# EmbeddedPeripherals.net
KiCad netlist of a schematic drawn in Altium Designer
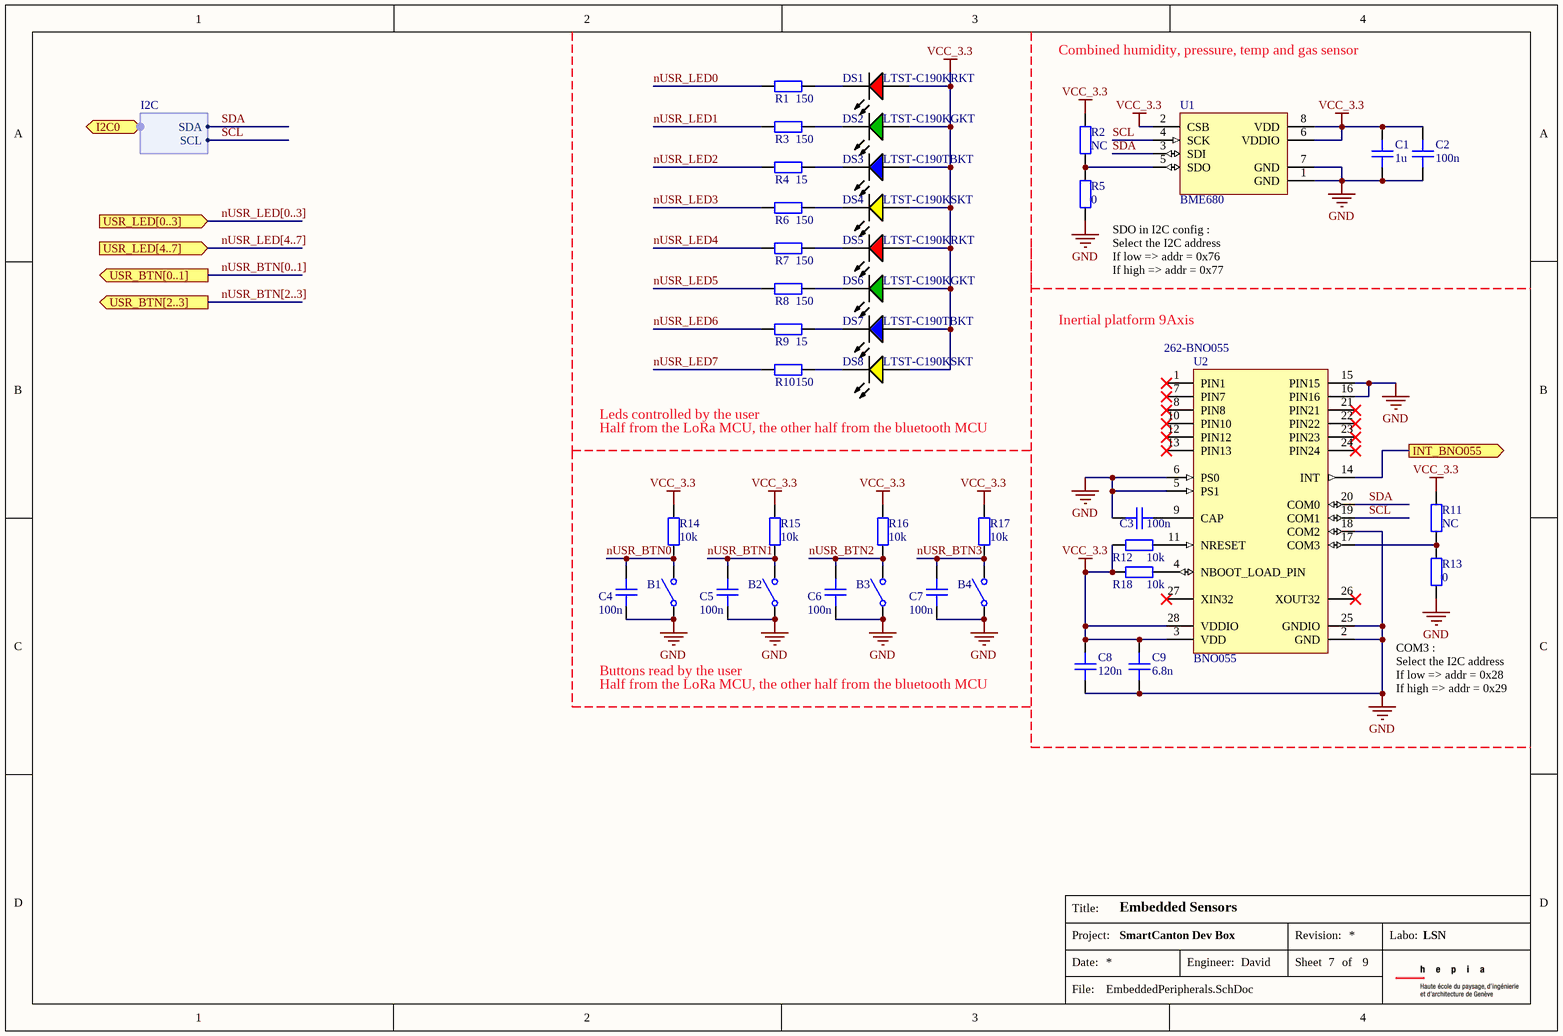
[diagram p0: EmbeddedPeripherals.SchDoc]

(export (version "E")
  (design (tool "Eeschema 10.0.6"))
  (components
    (comp (ref "B1")
      (value "653-B3U-1000P")
      (footprint "B3U-1000P")
      (libsource (lib "eSurf_handle") (part "PUSH_BUTTON"))
    )
    (comp (ref "B2")
      (value "653-B3U-1000P")
      (footprint "B3U-1000P")
      (libsource (lib "eSurf_handle") (part "PUSH_BUTTON"))
    )
    (comp (ref "B3")
      (value "653-B3U-1000P")
      (footprint "B3U-1000P")
      (libsource (lib "eSurf_handle") (part "PUSH_BUTTON"))
    )
    (comp (ref "B4")
      (value "653-B3U-1000P")
      (footprint "B3U-1000P")
      (libsource (lib "eSurf_handle") (part "PUSH_BUTTON"))
    )
    (comp (ref "C1")
      (value "1u")
      (footprint "CAPC1608X08")
      (description "MLCC Capacitor 1608")
      (libsource (lib "HEPIA Vault") (part "CMP-001-0010-A.3"))
    )
    (comp (ref "C2")
      (value "100n")
      (footprint "CAPC1608X08")
      (description "MLCC Capacitor 1608")
      (libsource (lib "HEPIA Vault") (part "Capacitor"))
    )
    (comp (ref "C3")
      (value "100n")
      (footprint "CAPC1608X08")
      (description "MLCC Capacitor 1608")
      (libsource (lib "HEPIA Vault") (part "CMP-001-0010-A.3"))
    )
    (comp (ref "C4")
      (value "100n")
      (footprint "CAPC1608X08")
      (description "MLCC Capacitor 1608")
      (libsource (lib "HEPIA Vault") (part "CMP-001-0010-A.3"))
    )
    (comp (ref "C5")
      (value "100n")
      (footprint "CAPC1608X08")
      (description "MLCC Capacitor 1608")
      (libsource (lib "HEPIA Vault") (part "CMP-001-0010-A.3"))
    )
    (comp (ref "C6")
      (value "100n")
      (footprint "CAPC1608X08")
      (description "MLCC Capacitor 1608")
      (libsource (lib "HEPIA Vault") (part "CMP-001-0010-A.3"))
    )
    (comp (ref "C7")
      (value "100n")
      (footprint "CAPC1608X08")
      (description "MLCC Capacitor 1608")
      (libsource (lib "HEPIA Vault") (part "CMP-001-0010-A.3"))
    )
    (comp (ref "C8")
      (value "120n")
      (footprint "CAPC1608X08")
      (description "MLCC Capacitor 1608")
      (libsource (lib "HEPIA Vault") (part "CMP-001-0010-A.3"))
    )
    (comp (ref "C9")
      (value "6.8n")
      (footprint "CAPC1608X08")
      (description "MLCC Capacitor 1608")
      (libsource (lib "HEPIA Vault") (part "CMP-001-0010-A.3"))
    )
    (comp (ref "DS1")
      (value "LTST-C190KRKT")
      (footprint "LTST-C191KRKT_V")
      (description "LED Uni-Color Red, 62.5 mW, 5 V, -30 to 85 degC, 2-Pin SMD, RoHS, Tape and Reel")
      (fields (field (name "TOLERANCE") "20%"))
      (libsource (lib "HEPIA Vault") (part "LED-RED-AK-2"))
    )
    (comp (ref "DS2")
      (value "LTST-C190KGKT")
      (footprint "LITE-ON-LTST-C190GKT-2_V")
      (description "LED Uni-Color Green, 75 mW, 5 V, -30 to 85 degC, 2-Pin SMD, RoHS, Tape and Reel")
      (fields (field (name "MANUFACTURER") "Lite-On"))
      (libsource (lib "HEPIA Vault") (part "LED_GREEN_A1K2-2"))
    )
    (comp (ref "DS3")
      (value "LTST-C190TBKT")
      (footprint "LTST-C190TBKT-2_V")
      (description "Single Color Chip LED, 2.8 to 3.8 V, 28 to 180 mcd, -20 to 80 degC, 2-Pin SMD, RoHS, Tape and Reel")
      (libsource (lib "HEPIA Vault") (part "LED-BLUE-AK-2"))
    )
    (comp (ref "DS4")
      (value "LTST-C190KSKT")
      (footprint "LTST-C190KSKT_V")
      (description "LED Uni-Color Yellow, 75 mW, 30 mA, -30 to 85 degC, 2-Pin SMD, RoHS, Tape and Reel")
      (fields (field (name "TOLERANCE") "1%"))
      (libsource (lib "HEPIA Vault") (part "LED-YELLOW-AK-2"))
    )
    (comp (ref "DS5")
      (value "LTST-C190KRKT")
      (footprint "LTST-C191KRKT_V")
      (description "LED Uni-Color Red, 62.5 mW, 5 V, -30 to 85 degC, 2-Pin SMD, RoHS, Tape and Reel")
      (fields (field (name "TOLERANCE") "20%"))
      (libsource (lib "HEPIA Vault") (part "LED-RED-AK-2"))
    )
    (comp (ref "DS6")
      (value "LTST-C190KGKT")
      (footprint "LITE-ON-LTST-C190GKT-2_V")
      (description "LED Uni-Color Green, 75 mW, 5 V, -30 to 85 degC, 2-Pin SMD, RoHS, Tape and Reel")
      (fields (field (name "MANUFACTURER") "Lite-On"))
      (libsource (lib "HEPIA Vault") (part "LED_GREEN_A1K2-2"))
    )
    (comp (ref "DS7")
      (value "LTST-C190TBKT")
      (footprint "LTST-C190TBKT-2_V")
      (description "Single Color Chip LED, 2.8 to 3.8 V, 28 to 180 mcd, -20 to 80 degC, 2-Pin SMD, RoHS, Tape and Reel")
      (libsource (lib "HEPIA Vault") (part "LED-BLUE-AK-2"))
    )
    (comp (ref "DS8")
      (value "LTST-C190KSKT")
      (footprint "LTST-C190KSKT_V")
      (description "LED Uni-Color Yellow, 75 mW, 30 mA, -30 to 85 degC, 2-Pin SMD, RoHS, Tape and Reel")
      (fields (field (name "TOLERANCE") "1%"))
      (libsource (lib "HEPIA Vault") (part "LED-YELLOW-AK-2"))
    )
    (comp (ref "R1")
      (value "150")
      (footprint "RESC1608X06")
      (description "1608 resistor")
      (libsource (lib "HEPIA Vault") (part "CMP-001-0005-A.4"))
    )
    (comp (ref "R2")
      (value "NC")
      (footprint "RESC1608X06")
      (description "1608 resistor")
      (libsource (lib "") (part "CMP-001-0005-A.4_1"))
    )
    (comp (ref "R3")
      (value "150")
      (footprint "RESC1608X06")
      (description "1608 resistor")
      (libsource (lib "HEPIA Vault") (part "CMP-001-0005-A.4"))
    )
    (comp (ref "R4")
      (value "15")
      (footprint "RESC1608X06")
      (description "1608 resistor")
      (libsource (lib "HEPIA Vault") (part "CMP-001-0005-A.4"))
    )
    (comp (ref "R5")
      (value "0")
      (footprint "RESC1608X06")
      (description "1608 resistor")
      (libsource (lib "") (part "CMP-001-0005-A.4_1"))
    )
    (comp (ref "R6")
      (value "150")
      (footprint "RESC1608X06")
      (description "1608 resistor")
      (libsource (lib "HEPIA Vault") (part "CMP-001-0005-A.4"))
    )
    (comp (ref "R7")
      (value "150")
      (footprint "RESC1608X06")
      (description "1608 resistor")
      (libsource (lib "HEPIA Vault") (part "CMP-001-0005-A.4"))
    )
    (comp (ref "R8")
      (value "150")
      (footprint "RESC1608X06")
      (description "1608 resistor")
      (libsource (lib "HEPIA Vault") (part "CMP-001-0005-A.4"))
    )
    (comp (ref "R9")
      (value "15")
      (footprint "RESC1608X06")
      (description "1608 resistor")
      (libsource (lib "HEPIA Vault") (part "CMP-001-0005-A.4"))
    )
    (comp (ref "R10")
      (value "150")
      (footprint "RESC1608X06")
      (description "1608 resistor")
      (libsource (lib "HEPIA Vault") (part "CMP-001-0005-A.4"))
    )
    (comp (ref "R11")
      (value "NC")
      (footprint "RESC1608X06")
      (description "1608 resistor")
      (libsource (lib "") (part "CMP-001-0005-A.4_1"))
    )
    (comp (ref "R12")
      (value "10k")
      (footprint "RESC1608X06")
      (description "1608 resistor")
      (libsource (lib "HEPIA Vault") (part "CMP-001-0005-A.4"))
    )
    (comp (ref "R13")
      (value "0")
      (footprint "RESC1608X06")
      (description "1608 resistor")
      (libsource (lib "") (part "CMP-001-0005-A.4_1"))
    )
    (comp (ref "R14")
      (value "10k")
      (footprint "RESC1608X06")
      (description "1608 resistor")
      (libsource (lib "") (part "CMP-001-0005-A.4_1"))
    )
    (comp (ref "R15")
      (value "10k")
      (footprint "RESC1608X06")
      (description "1608 resistor")
      (libsource (lib "") (part "CMP-001-0005-A.4_1"))
    )
    (comp (ref "R16")
      (value "10k")
      (footprint "RESC1608X06")
      (description "1608 resistor")
      (libsource (lib "") (part "CMP-001-0005-A.4_1"))
    )
    (comp (ref "R17")
      (value "10k")
      (footprint "RESC1608X06")
      (description "1608 resistor")
      (libsource (lib "") (part "CMP-001-0005-A.4_1"))
    )
    (comp (ref "R18")
      (value "10k")
      (footprint "RESC1608X06")
      (description "1608 resistor")
      (libsource (lib "HEPIA Vault") (part "CMP-001-0005-A.4"))
    )
    (comp (ref "U1")
      (value "BME680")
      (footprint "LGA-8-30x30x09")
      (description "Combined himidity, pressure, temp and gas sensor")
      (libsource (lib "HEPIA Vault") (part "BME680"))
    )
    (comp (ref "U2")
      (value "BNO055")
      (footprint "BOSC-LGA-28_N")
      (fields
        (field (name "MANUFACTURER") "Bosch Sensortec")
        (field (name "SUPPLIER PART NUMBER 1") "262-BNO055")
      )
      (libsource (lib "HEPIA Vault") (part "CMP-00007-A.1"))
    )
  )
  (nets
    (net (code "2") (name "/INT_BNO055") (class "Default")
      (node (ref "U2") (pin "14") (pinfunction "INT_14") (pintype "output"))
    )
    (net (code "3") (name "/SCL") (class "Default")
      (node (ref "U1") (pin "4") (pinfunction "SCK_4") (pintype "input"))
      (node (ref "U2") (pin "19") (pinfunction "COM1_19") (pintype "bidirectional"))
    )
    (net (code "4") (name "/SDA") (class "Default")
      (node (ref "U1") (pin "3") (pinfunction "SDI_3") (pintype "bidirectional"))
      (node (ref "U2") (pin "20") (pinfunction "COM0_20") (pintype "bidirectional"))
    )
    (net (code "5") (name "/nUSR_BTN0") (class "Default")
      (node (ref "B1") (pin "2") (pinfunction "2_2") (pintype "passive"))
      (node (ref "C4") (pin "1") (pinfunction "1_1") (pintype "passive"))
      (node (ref "R14") (pin "1") (pinfunction "1_1") (pintype "passive"))
    )
    (net (code "6") (name "/nUSR_BTN1") (class "Default")
      (node (ref "B2") (pin "2") (pinfunction "2_2") (pintype "passive"))
      (node (ref "C5") (pin "1") (pinfunction "1_1") (pintype "passive"))
      (node (ref "R15") (pin "1") (pinfunction "1_1") (pintype "passive"))
    )
    (net (code "7") (name "/nUSR_BTN2") (class "Default")
      (node (ref "B3") (pin "2") (pinfunction "2_2") (pintype "passive"))
      (node (ref "C6") (pin "1") (pinfunction "1_1") (pintype "passive"))
      (node (ref "R16") (pin "1") (pinfunction "1_1") (pintype "passive"))
    )
    (net (code "8") (name "/nUSR_BTN3") (class "Default")
      (node (ref "B4") (pin "2") (pinfunction "2_2") (pintype "passive"))
      (node (ref "C7") (pin "1") (pinfunction "1_1") (pintype "passive"))
      (node (ref "R17") (pin "1") (pinfunction "1_1") (pintype "passive"))
    )
    (net (code "11") (name "/nUSR_LED0") (class "Default")
      (node (ref "R1") (pin "1") (pinfunction "1_1") (pintype "passive"))
    )
    (net (code "12") (name "/nUSR_LED1") (class "Default")
      (node (ref "R3") (pin "1") (pinfunction "1_1") (pintype "passive"))
    )
    (net (code "13") (name "/nUSR_LED2") (class "Default")
      (node (ref "R4") (pin "1") (pinfunction "1_1") (pintype "passive"))
    )
    (net (code "14") (name "/nUSR_LED3") (class "Default")
      (node (ref "R6") (pin "1") (pinfunction "1_1") (pintype "passive"))
    )
    (net (code "15") (name "/nUSR_LED4") (class "Default")
      (node (ref "R7") (pin "1") (pinfunction "1_1") (pintype "passive"))
    )
    (net (code "16") (name "/nUSR_LED5") (class "Default")
      (node (ref "R8") (pin "1") (pinfunction "1_1") (pintype "passive"))
    )
    (net (code "17") (name "/nUSR_LED6") (class "Default")
      (node (ref "R9") (pin "1") (pinfunction "1_1") (pintype "passive"))
    )
    (net (code "18") (name "/nUSR_LED7") (class "Default")
      (node (ref "R10") (pin "1") (pinfunction "1_1") (pintype "passive"))
    )
    (net (code "22") (name "GND") (class "Default")
      (node (ref "B1") (pin "1") (pinfunction "1_1") (pintype "passive"))
      (node (ref "B2") (pin "1") (pinfunction "1_1") (pintype "passive"))
      (node (ref "B3") (pin "1") (pinfunction "1_1") (pintype "passive"))
      (node (ref "B4") (pin "1") (pinfunction "1_1") (pintype "passive"))
      (node (ref "C1") (pin "1") (pinfunction "1_1") (pintype "passive"))
      (node (ref "C2") (pin "1") (pinfunction "1_1") (pintype "passive"))
      (node (ref "C3") (pin "2") (pinfunction "2_2") (pintype "passive"))
      (node (ref "C4") (pin "2") (pinfunction "2_2") (pintype "passive"))
      (node (ref "C5") (pin "2") (pinfunction "2_2") (pintype "passive"))
      (node (ref "C6") (pin "2") (pinfunction "2_2") (pintype "passive"))
      (node (ref "C7") (pin "2") (pinfunction "2_2") (pintype "passive"))
      (node (ref "C8") (pin "1") (pinfunction "1_1") (pintype "passive"))
      (node (ref "C9") (pin "1") (pinfunction "1_1") (pintype "passive"))
      (node (ref "R13") (pin "1") (pinfunction "1_1") (pintype "passive"))
      (node (ref "R5") (pin "1") (pinfunction "1_1") (pintype "passive"))
      (node (ref "U1") (pin "1") (pinfunction "GND_1") (pintype "power_in"))
      (node (ref "U1") (pin "7") (pinfunction "GND_7") (pintype "power_in"))
      (node (ref "U2") (pin "15") (pinfunction "PIN15_15") (pintype "power_in"))
      (node (ref "U2") (pin "16") (pinfunction "PIN16_16") (pintype "power_in"))
      (node (ref "U2") (pin "18") (pinfunction "COM2_18") (pintype "bidirectional"))
      (node (ref "U2") (pin "2") (pinfunction "GND_2") (pintype "power_in"))
      (node (ref "U2") (pin "25") (pinfunction "GNDIO_25") (pintype "power_in"))
      (node (ref "U2") (pin "5") (pinfunction "PS1_5") (pintype "input"))
      (node (ref "U2") (pin "6") (pinfunction "PS0_6") (pintype "input"))
    )
    (net (code "23") (name "Net-(DS1-K)") (class "Default")
      (node (ref "DS1") (pin "2") (pinfunction "K_2") (pintype "passive"))
      (node (ref "R1") (pin "2") (pinfunction "2_2") (pintype "passive"))
    )
    (net (code "24") (name "Net-(DS2-K)") (class "Default")
      (node (ref "DS2") (pin "2") (pinfunction "K_2") (pintype "passive"))
      (node (ref "R3") (pin "2") (pinfunction "2_2") (pintype "passive"))
    )
    (net (code "25") (name "Net-(DS3-K)") (class "Default")
      (node (ref "DS3") (pin "2") (pinfunction "K_2") (pintype "passive"))
      (node (ref "R4") (pin "2") (pinfunction "2_2") (pintype "passive"))
    )
    (net (code "26") (name "Net-(DS4-K)") (class "Default")
      (node (ref "DS4") (pin "2") (pinfunction "K_2") (pintype "passive"))
      (node (ref "R6") (pin "2") (pinfunction "2_2") (pintype "passive"))
    )
    (net (code "27") (name "Net-(DS5-K)") (class "Default")
      (node (ref "DS5") (pin "2") (pinfunction "K_2") (pintype "passive"))
      (node (ref "R7") (pin "2") (pinfunction "2_2") (pintype "passive"))
    )
    (net (code "28") (name "Net-(DS6-K)") (class "Default")
      (node (ref "DS6") (pin "2") (pinfunction "K_2") (pintype "passive"))
      (node (ref "R8") (pin "2") (pinfunction "2_2") (pintype "passive"))
    )
    (net (code "29") (name "Net-(DS7-K)") (class "Default")
      (node (ref "DS7") (pin "2") (pinfunction "K_2") (pintype "passive"))
      (node (ref "R9") (pin "2") (pinfunction "2_2") (pintype "passive"))
    )
    (net (code "30") (name "Net-(DS8-K)") (class "Default")
      (node (ref "DS8") (pin "2") (pinfunction "K_2") (pintype "passive"))
      (node (ref "R10") (pin "2") (pinfunction "2_2") (pintype "passive"))
    )
    (net (code "31") (name "Net-(U1-SDO)") (class "Default")
      (node (ref "R2") (pin "1") (pinfunction "1_1") (pintype "passive"))
      (node (ref "R5") (pin "2") (pinfunction "2_2") (pintype "passive"))
      (node (ref "U1") (pin "5") (pinfunction "SDO_5") (pintype "bidirectional"))
    )
    (net (code "32") (name "Net-(U2-CAP)") (class "Default")
      (node (ref "C3") (pin "1") (pinfunction "1_1") (pintype "passive"))
      (node (ref "U2") (pin "9") (pinfunction "CAP_9") (pintype "passive"))
    )
    (net (code "33") (name "Net-(U2-COM3)") (class "Default")
      (node (ref "R11") (pin "1") (pinfunction "1_1") (pintype "passive"))
      (node (ref "R13") (pin "2") (pinfunction "2_2") (pintype "passive"))
      (node (ref "U2") (pin "17") (pinfunction "COM3_17") (pintype "bidirectional"))
    )
    (net (code "34") (name "Net-(U2-NBOOT_LOAD_PIN)") (class "Default")
      (node (ref "R18") (pin "2") (pinfunction "2_2") (pintype "passive"))
      (node (ref "U2") (pin "4") (pinfunction "NBOOT_LOAD_PIN_4") (pintype "bidirectional"))
    )
    (net (code "35") (name "Net-(U2-NRESET)") (class "Default")
      (node (ref "R12") (pin "2") (pinfunction "2_2") (pintype "passive"))
      (node (ref "U2") (pin "11") (pinfunction "NRESET_11") (pintype "input"))
    )
    (net (code "36") (name "VCC_3.3") (class "Default")
      (node (ref "C1") (pin "2") (pinfunction "2_2") (pintype "passive"))
      (node (ref "C2") (pin "2") (pinfunction "2_2") (pintype "passive"))
      (node (ref "C8") (pin "2") (pinfunction "2_2") (pintype "passive"))
      (node (ref "C9") (pin "2") (pinfunction "2_2") (pintype "passive"))
      (node (ref "DS1") (pin "1") (pinfunction "A_1") (pintype "passive"))
      (node (ref "DS2") (pin "1") (pinfunction "A_1") (pintype "passive"))
      (node (ref "DS3") (pin "1") (pinfunction "A_1") (pintype "passive"))
      (node (ref "DS4") (pin "1") (pinfunction "A_1") (pintype "passive"))
      (node (ref "DS5") (pin "1") (pinfunction "A_1") (pintype "passive"))
      (node (ref "DS6") (pin "1") (pinfunction "A_1") (pintype "passive"))
      (node (ref "DS7") (pin "1") (pinfunction "A_1") (pintype "passive"))
      (node (ref "DS8") (pin "1") (pinfunction "A_1") (pintype "passive"))
      (node (ref "R11") (pin "2") (pinfunction "2_2") (pintype "passive"))
      (node (ref "R12") (pin "1") (pinfunction "1_1") (pintype "passive"))
      (node (ref "R14") (pin "2") (pinfunction "2_2") (pintype "passive"))
      (node (ref "R15") (pin "2") (pinfunction "2_2") (pintype "passive"))
      (node (ref "R16") (pin "2") (pinfunction "2_2") (pintype "passive"))
      (node (ref "R17") (pin "2") (pinfunction "2_2") (pintype "passive"))
      (node (ref "R18") (pin "1") (pinfunction "1_1") (pintype "passive"))
      (node (ref "R2") (pin "2") (pinfunction "2_2") (pintype "passive"))
      (node (ref "U1") (pin "2") (pinfunction "CSB_2") (pintype "passive"))
      (node (ref "U1") (pin "6") (pinfunction "VDDIO_6") (pintype "power_in"))
      (node (ref "U1") (pin "8") (pinfunction "VDD_8") (pintype "power_in"))
      (node (ref "U2") (pin "28") (pinfunction "VDDIO_28") (pintype "power_in"))
      (node (ref "U2") (pin "3") (pinfunction "VDD_3") (pintype "power_in"))
    )
    (net (code "37") (name "unconnected-(U2-PIN1-Pad1)") (class "Default")
      (node (ref "U2") (pin "1") (pinfunction "PIN1_1") (pintype "passive+no_connect"))
    )
    (net (code "38") (name "unconnected-(U2-PIN7-Pad7)") (class "Default")
      (node (ref "U2") (pin "7") (pinfunction "PIN7_7") (pintype "passive+no_connect"))
    )
    (net (code "39") (name "unconnected-(U2-PIN8-Pad8)") (class "Default")
      (node (ref "U2") (pin "8") (pinfunction "PIN8_8") (pintype "passive+no_connect"))
    )
    (net (code "40") (name "unconnected-(U2-PIN10-Pad10)") (class "Default")
      (node (ref "U2") (pin "10") (pinfunction "PIN10_10") (pintype "power_in+no_connect"))
    )
    (net (code "41") (name "unconnected-(U2-PIN12-Pad12)") (class "Default")
      (node (ref "U2") (pin "12") (pinfunction "PIN12_12") (pintype "passive+no_connect"))
    )
    (net (code "42") (name "unconnected-(U2-PIN13-Pad13)") (class "Default")
      (node (ref "U2") (pin "13") (pinfunction "PIN13_13") (pintype "passive+no_connect"))
    )
    (net (code "43") (name "unconnected-(U2-PIN21-Pad21)") (class "Default")
      (node (ref "U2") (pin "21") (pinfunction "PIN21_21") (pintype "passive+no_connect"))
    )
    (net (code "44") (name "unconnected-(U2-PIN22-Pad22)") (class "Default")
      (node (ref "U2") (pin "22") (pinfunction "PIN22_22") (pintype "passive+no_connect"))
    )
    (net (code "45") (name "unconnected-(U2-PIN23-Pad23)") (class "Default")
      (node (ref "U2") (pin "23") (pinfunction "PIN23_23") (pintype "passive+no_connect"))
    )
    (net (code "46") (name "unconnected-(U2-PIN24-Pad24)") (class "Default")
      (node (ref "U2") (pin "24") (pinfunction "PIN24_24") (pintype "passive+no_connect"))
    )
    (net (code "47") (name "unconnected-(U2-XIN32-Pad27)") (class "Default")
      (node (ref "U2") (pin "27") (pinfunction "XIN32_27") (pintype "passive+no_connect"))
    )
    (net (code "48") (name "unconnected-(U2-XOUT32-Pad26)") (class "Default")
      (node (ref "U2") (pin "26") (pinfunction "XOUT32_26") (pintype "passive+no_connect"))
    )
  )
)
